# Sensormount.net
KiCad netlist of a schematic drawn in EAGLE
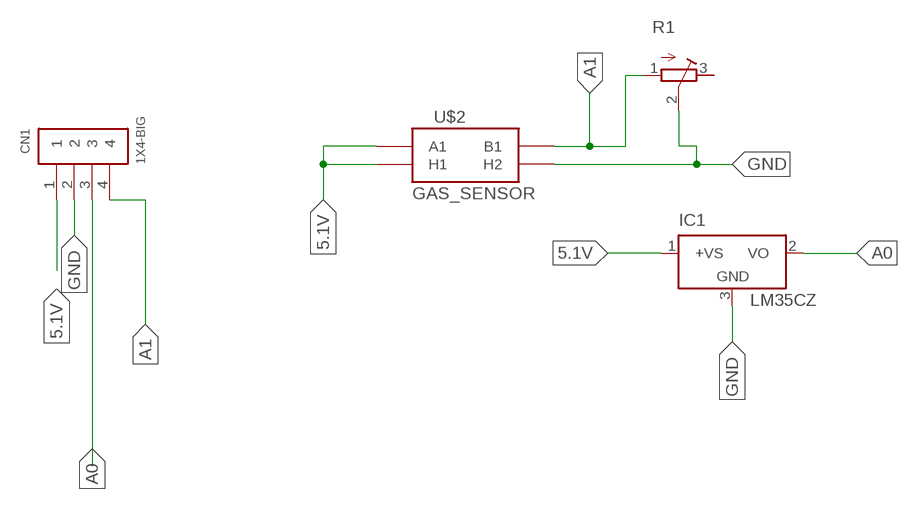
[diagram p0: schematic, sheet 1]

(export (version "E")
  (design (tool "Eeschema 10.0.6"))
  (components
    (comp (ref "CN1")
      (value "1X4-BIG")
      (footprint "eagle-import:1X04-BIG")
      (libsource (lib "eagle-import") (part "1X4-BIG"))
    )
    (comp (ref "IC1")
      (value "LM35CZ")
      (footprint "eagle-import:TO92")
      (libsource (lib "eagle-import") (part "LM35CZ"))
    )
    (comp (ref "R1")
      (value "R-TRIMM64W")
      (footprint "eagle-import:RTRIM64W")
      (libsource (lib "eagle-import") (part "R-TRIMM64W"))
    )
    (comp (ref "U$2")
      (value "GAS_SENSOR")
      (footprint "eagle-import:MQ-3")
      (libsource (lib "eagle-import") (part "GAS_SENSOR"))
    )
  )
  (nets
    (net (code "1") (name "5.1V") (class "Default")
      (node (ref "CN1") (pin "1") (pinfunction "1_1") (pintype "bidirectional"))
      (node (ref "IC1") (pin "1") (pinfunction "+VS_1") (pintype "input"))
      (node (ref "U$2") (pin "A1") (pinfunction "A1_A1") (pintype "bidirectional"))
      (node (ref "U$2") (pin "HA") (pinfunction "H1_HA") (pintype "bidirectional"))
    )
    (net (code "2") (name "A0") (class "Default")
      (node (ref "CN1") (pin "3") (pinfunction "3_3") (pintype "bidirectional"))
      (node (ref "IC1") (pin "2") (pinfunction "VO_2") (pintype "input"))
    )
    (net (code "3") (name "A1") (class "Default")
      (node (ref "CN1") (pin "4") (pinfunction "4_4") (pintype "bidirectional"))
      (node (ref "R1") (pin "1") (pinfunction "A_1") (pintype "passive"))
      (node (ref "U$2") (pin "B1") (pinfunction "B1_B1") (pintype "bidirectional"))
    )
    (net (code "4") (name "GND") (class "Default")
      (node (ref "CN1") (pin "2") (pinfunction "2_2") (pintype "bidirectional"))
      (node (ref "IC1") (pin "3") (pinfunction "GND_3") (pintype "power_in"))
      (node (ref "R1") (pin "2") (pinfunction "S_2") (pintype "passive"))
      (node (ref "U$2") (pin "HB") (pinfunction "H2_HB") (pintype "bidirectional"))
    )
    (net (code "5") (name "unconnected-(R1-E-Pad3)") (class "Default")
      (node (ref "R1") (pin "3") (pinfunction "E_3") (pintype "passive"))
    )
  )
)
